# USB23DO.net
KiCad netlist of a schematic drawn in EAGLE
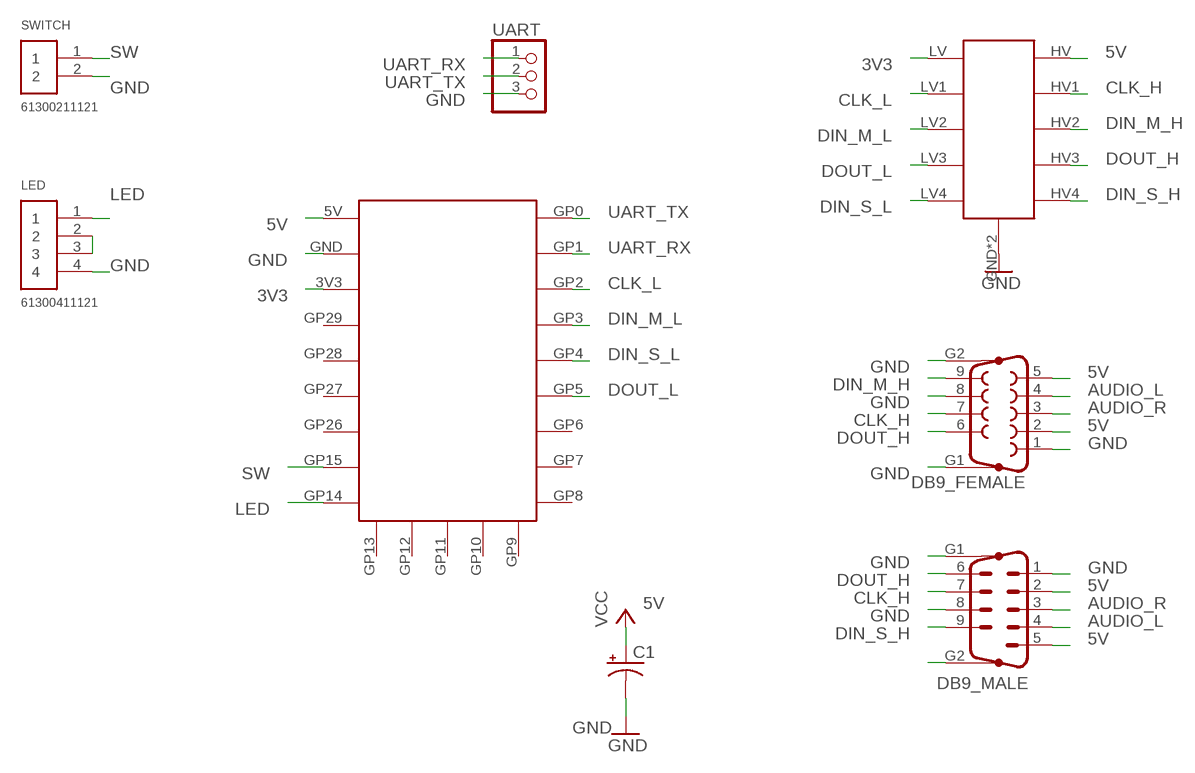
[diagram p0: schematic, sheet 1]

(export (version "E")
  (design (tool "Eeschema 10.0.6"))
  (components
    (comp (ref "C1")
      (value "CPOL-USB45181A")
      (footprint "eagle-import:B45181A")
      (libsource (lib "eagle-import") (part "CPOL-USB45181A"))
    )
    (comp (ref "DB9_FEMALE")
      (value "F09HP")
      (footprint "eagle-import:F09HP")
      (libsource (lib "eagle-import") (part "F09HP"))
    )
    (comp (ref "DB9_MALE")
      (value "M09HP")
      (footprint "eagle-import:M09HP")
      (libsource (lib "eagle-import") (part "M09HP"))
    )
    (comp (ref "LED")
      (value "61300411121")
      (footprint "eagle-import:61300411121")
      (fields
        (field (name "DIGI_KEY_PART_NUMBER") "732-5317-ND")
        (field (name "MANUFACTURER") "Wurth Electronics Inc.")
        (field (name "CREATED_BY") "PCBLayout.com")
      )
      (libsource (lib "eagle-import") (part "61300411121"))
    )
    (comp (ref "LVL_SHIFTER")
      (value "4WAYS_LEVEL_SHIFTER")
      (footprint "eagle-import:4WAYS_LEVEL_SHIFTER")
      (libsource (lib "eagle-import") (part "4WAYS_LEVEL_SHIFTER"))
    )
    (comp (ref "RP2040-ZERO")
      (value "WAVESHARE_RP_2040_ZERO")
      (footprint "eagle-import:WAVESHARE_RP_2040_ZERO")
      (libsource (lib "eagle-import") (part "WAVESHARE_RP_2040_ZERO"))
    )
    (comp (ref "SWITCH")
      (value "61300211121")
      (footprint "eagle-import:61300211121")
      (fields
        (field (name "DIGI_KEY_PART_NUMBER") "732-5315-ND")
        (field (name "MANUFACTURER") "Wurth Electronics Inc.")
        (field (name "CREATED_BY") "PCBLayout.com")
      )
      (libsource (lib "eagle-import") (part "61300211121"))
    )
    (comp (ref "UART")
      (value "PINHD-1X3CB")
      (footprint "eagle-import:1X03-CLEANBIG")
      (libsource (lib "eagle-import") (part "PINHD-1X3CB"))
    )
  )
  (nets
    (net (code "1") (name "/3V3") (class "Default")
      (node (ref "LVL_SHIFTER") (pin "LV") (pinfunction "LV_LV") (pintype "bidirectional"))
      (node (ref "RP2040-ZERO") (pin "3V3") (pinfunction "3V3_3V3") (pintype "bidirectional"))
    )
    (net (code "2") (name "/AUDIO_L") (class "Default")
      (node (ref "DB9_FEMALE") (pin "4") (pinfunction "4_4") (pintype "passive"))
      (node (ref "DB9_MALE") (pin "4") (pinfunction "4_4") (pintype "passive"))
    )
    (net (code "3") (name "/AUDIO_R") (class "Default")
      (node (ref "DB9_FEMALE") (pin "3") (pinfunction "3_3") (pintype "passive"))
      (node (ref "DB9_MALE") (pin "3") (pinfunction "3_3") (pintype "passive"))
    )
    (net (code "4") (name "/CLK_H") (class "Default")
      (node (ref "DB9_FEMALE") (pin "7") (pinfunction "7_7") (pintype "passive"))
      (node (ref "DB9_MALE") (pin "7") (pinfunction "7_7") (pintype "passive"))
      (node (ref "LVL_SHIFTER") (pin "HV1") (pinfunction "HV1_HV1") (pintype "bidirectional"))
    )
    (net (code "5") (name "/CLK_L") (class "Default")
      (node (ref "LVL_SHIFTER") (pin "LV1") (pinfunction "LV1_LV1") (pintype "bidirectional"))
      (node (ref "RP2040-ZERO") (pin "GP2") (pinfunction "GP2_GP2") (pintype "bidirectional"))
    )
    (net (code "6") (name "/DIN_M_H") (class "Default")
      (node (ref "DB9_FEMALE") (pin "9") (pinfunction "9_9") (pintype "passive"))
      (node (ref "LVL_SHIFTER") (pin "HV2") (pinfunction "HV2_HV2") (pintype "bidirectional"))
    )
    (net (code "7") (name "/DIN_M_L") (class "Default")
      (node (ref "LVL_SHIFTER") (pin "LV2") (pinfunction "LV2_LV2") (pintype "bidirectional"))
      (node (ref "RP2040-ZERO") (pin "GP3") (pinfunction "GP3_GP3") (pintype "bidirectional"))
    )
    (net (code "8") (name "/DIN_S_H") (class "Default")
      (node (ref "DB9_MALE") (pin "9") (pinfunction "9_9") (pintype "passive"))
      (node (ref "LVL_SHIFTER") (pin "HV4") (pinfunction "HV4_HV4") (pintype "bidirectional"))
    )
    (net (code "9") (name "/DIN_S_L") (class "Default")
      (node (ref "LVL_SHIFTER") (pin "LV4") (pinfunction "LV4_LV4") (pintype "bidirectional"))
      (node (ref "RP2040-ZERO") (pin "GP4") (pinfunction "GP4_GP4") (pintype "bidirectional"))
    )
    (net (code "10") (name "/DOUT_H") (class "Default")
      (node (ref "DB9_FEMALE") (pin "6") (pinfunction "6_6") (pintype "passive"))
      (node (ref "DB9_MALE") (pin "6") (pinfunction "6_6") (pintype "passive"))
      (node (ref "LVL_SHIFTER") (pin "HV3") (pinfunction "HV3_HV3") (pintype "bidirectional"))
    )
    (net (code "11") (name "/DOUT_L") (class "Default")
      (node (ref "LVL_SHIFTER") (pin "LV3") (pinfunction "LV3_LV3") (pintype "bidirectional"))
      (node (ref "RP2040-ZERO") (pin "GP5") (pinfunction "GP5_GP5") (pintype "bidirectional"))
    )
    (net (code "12") (name "/LED") (class "Default")
      (node (ref "LED") (pin "1") (pinfunction "1_1") (pintype "passive"))
      (node (ref "RP2040-ZERO") (pin "GP14") (pinfunction "GP14_GP14") (pintype "bidirectional"))
    )
    (net (code "13") (name "/SW") (class "Default")
      (node (ref "RP2040-ZERO") (pin "GP15") (pinfunction "GP15_GP15") (pintype "bidirectional"))
      (node (ref "SWITCH") (pin "1") (pinfunction "1_1") (pintype "passive"))
    )
    (net (code "14") (name "/UART_RX") (class "Default")
      (node (ref "RP2040-ZERO") (pin "GP1") (pinfunction "GP1_GP1") (pintype "bidirectional"))
      (node (ref "UART") (pin "1") (pinfunction "1_1") (pintype "passive"))
    )
    (net (code "15") (name "/UART_TX") (class "Default")
      (node (ref "RP2040-ZERO") (pin "GP0") (pinfunction "GP0_GP0") (pintype "bidirectional"))
      (node (ref "UART") (pin "2") (pinfunction "2_2") (pintype "passive"))
    )
    (net (code "16") (name "GND") (class "Default")
      (node (ref "C1") (pin "-") (pinfunction "-_-") (pintype "passive"))
      (node (ref "DB9_FEMALE") (pin "1") (pinfunction "1_1") (pintype "passive"))
      (node (ref "DB9_FEMALE") (pin "8") (pinfunction "8_8") (pintype "passive"))
      (node (ref "DB9_FEMALE") (pin "G1") (pinfunction "G1_G1") (pintype "passive"))
      (node (ref "DB9_FEMALE") (pin "G2") (pinfunction "G2_G2") (pintype "passive"))
      (node (ref "DB9_MALE") (pin "1") (pinfunction "1_1") (pintype "passive"))
      (node (ref "DB9_MALE") (pin "8") (pinfunction "8_8") (pintype "passive"))
      (node (ref "DB9_MALE") (pin "G1") (pinfunction "G1_G1") (pintype "passive"))
      (node (ref "LED") (pin "4") (pinfunction "4_4") (pintype "passive"))
      (node (ref "LVL_SHIFTER") (pin "GND") (pinfunction "GND_GND") (pintype "bidirectional"))
      (node (ref "LVL_SHIFTER") (pin "GND_1") (pinfunction "GND_GND_1") (pintype "bidirectional"))
      (node (ref "RP2040-ZERO") (pin "GND") (pinfunction "GND_GND") (pintype "bidirectional"))
      (node (ref "SWITCH") (pin "2") (pinfunction "2_2") (pintype "passive"))
      (node (ref "UART") (pin "3") (pinfunction "3_3") (pintype "passive"))
    )
    (net (code "17") (name "Net-(LED-Pad2)") (class "Default")
      (node (ref "LED") (pin "2") (pinfunction "2_2") (pintype "passive"))
      (node (ref "LED") (pin "3") (pinfunction "3_3") (pintype "passive"))
    )
    (net (code "18") (name "VCC") (class "Default")
      (node (ref "C1") (pin "+") (pinfunction "+_+") (pintype "passive"))
      (node (ref "DB9_FEMALE") (pin "2") (pinfunction "2_2") (pintype "passive"))
      (node (ref "DB9_FEMALE") (pin "5") (pinfunction "5_5") (pintype "passive"))
      (node (ref "DB9_MALE") (pin "2") (pinfunction "2_2") (pintype "passive"))
      (node (ref "DB9_MALE") (pin "5") (pinfunction "5_5") (pintype "passive"))
      (node (ref "LVL_SHIFTER") (pin "HV") (pinfunction "HV_HV") (pintype "bidirectional"))
      (node (ref "RP2040-ZERO") (pin "5V") (pinfunction "5V_5V") (pintype "bidirectional"))
    )
    (net (code "19") (name "unconnected-(DB9_MALE-PadG2)") (class "Default")
      (node (ref "DB9_MALE") (pin "G2") (pinfunction "G2_G2") (pintype "passive"))
    )
    (net (code "20") (name "unconnected-(RP2040-ZERO-PadGP6)") (class "Default")
      (node (ref "RP2040-ZERO") (pin "GP6") (pinfunction "GP6_GP6") (pintype "bidirectional"))
    )
    (net (code "21") (name "unconnected-(RP2040-ZERO-PadGP7)") (class "Default")
      (node (ref "RP2040-ZERO") (pin "GP7") (pinfunction "GP7_GP7") (pintype "bidirectional"))
    )
    (net (code "22") (name "unconnected-(RP2040-ZERO-PadGP8)") (class "Default")
      (node (ref "RP2040-ZERO") (pin "GP8") (pinfunction "GP8_GP8") (pintype "bidirectional"))
    )
    (net (code "23") (name "unconnected-(RP2040-ZERO-PadGP9)") (class "Default")
      (node (ref "RP2040-ZERO") (pin "GP9") (pinfunction "GP9_GP9") (pintype "bidirectional"))
    )
    (net (code "24") (name "unconnected-(RP2040-ZERO-PadGP10)") (class "Default")
      (node (ref "RP2040-ZERO") (pin "GP10") (pinfunction "GP10_GP10") (pintype "bidirectional"))
    )
    (net (code "25") (name "unconnected-(RP2040-ZERO-PadGP11)") (class "Default")
      (node (ref "RP2040-ZERO") (pin "GP11") (pinfunction "GP11_GP11") (pintype "bidirectional"))
    )
    (net (code "26") (name "unconnected-(RP2040-ZERO-PadGP12)") (class "Default")
      (node (ref "RP2040-ZERO") (pin "GP12") (pinfunction "GP12_GP12") (pintype "bidirectional"))
    )
    (net (code "27") (name "unconnected-(RP2040-ZERO-PadGP13)") (class "Default")
      (node (ref "RP2040-ZERO") (pin "GP13") (pinfunction "GP13_GP13") (pintype "bidirectional"))
    )
    (net (code "28") (name "unconnected-(RP2040-ZERO-PadGP26)") (class "Default")
      (node (ref "RP2040-ZERO") (pin "GP26") (pinfunction "GP26_GP26") (pintype "bidirectional"))
    )
    (net (code "29") (name "unconnected-(RP2040-ZERO-PadGP27)") (class "Default")
      (node (ref "RP2040-ZERO") (pin "GP27") (pinfunction "GP27_GP27") (pintype "bidirectional"))
    )
    (net (code "30") (name "unconnected-(RP2040-ZERO-PadGP28)") (class "Default")
      (node (ref "RP2040-ZERO") (pin "GP28") (pinfunction "GP28_GP28") (pintype "bidirectional"))
    )
    (net (code "31") (name "unconnected-(RP2040-ZERO-PadGP29)") (class "Default")
      (node (ref "RP2040-ZERO") (pin "GP29") (pinfunction "GP29_GP29") (pintype "bidirectional"))
    )
  )
)
